# LPDDR4.net
KiCad netlist of a schematic drawn in Altium Designer
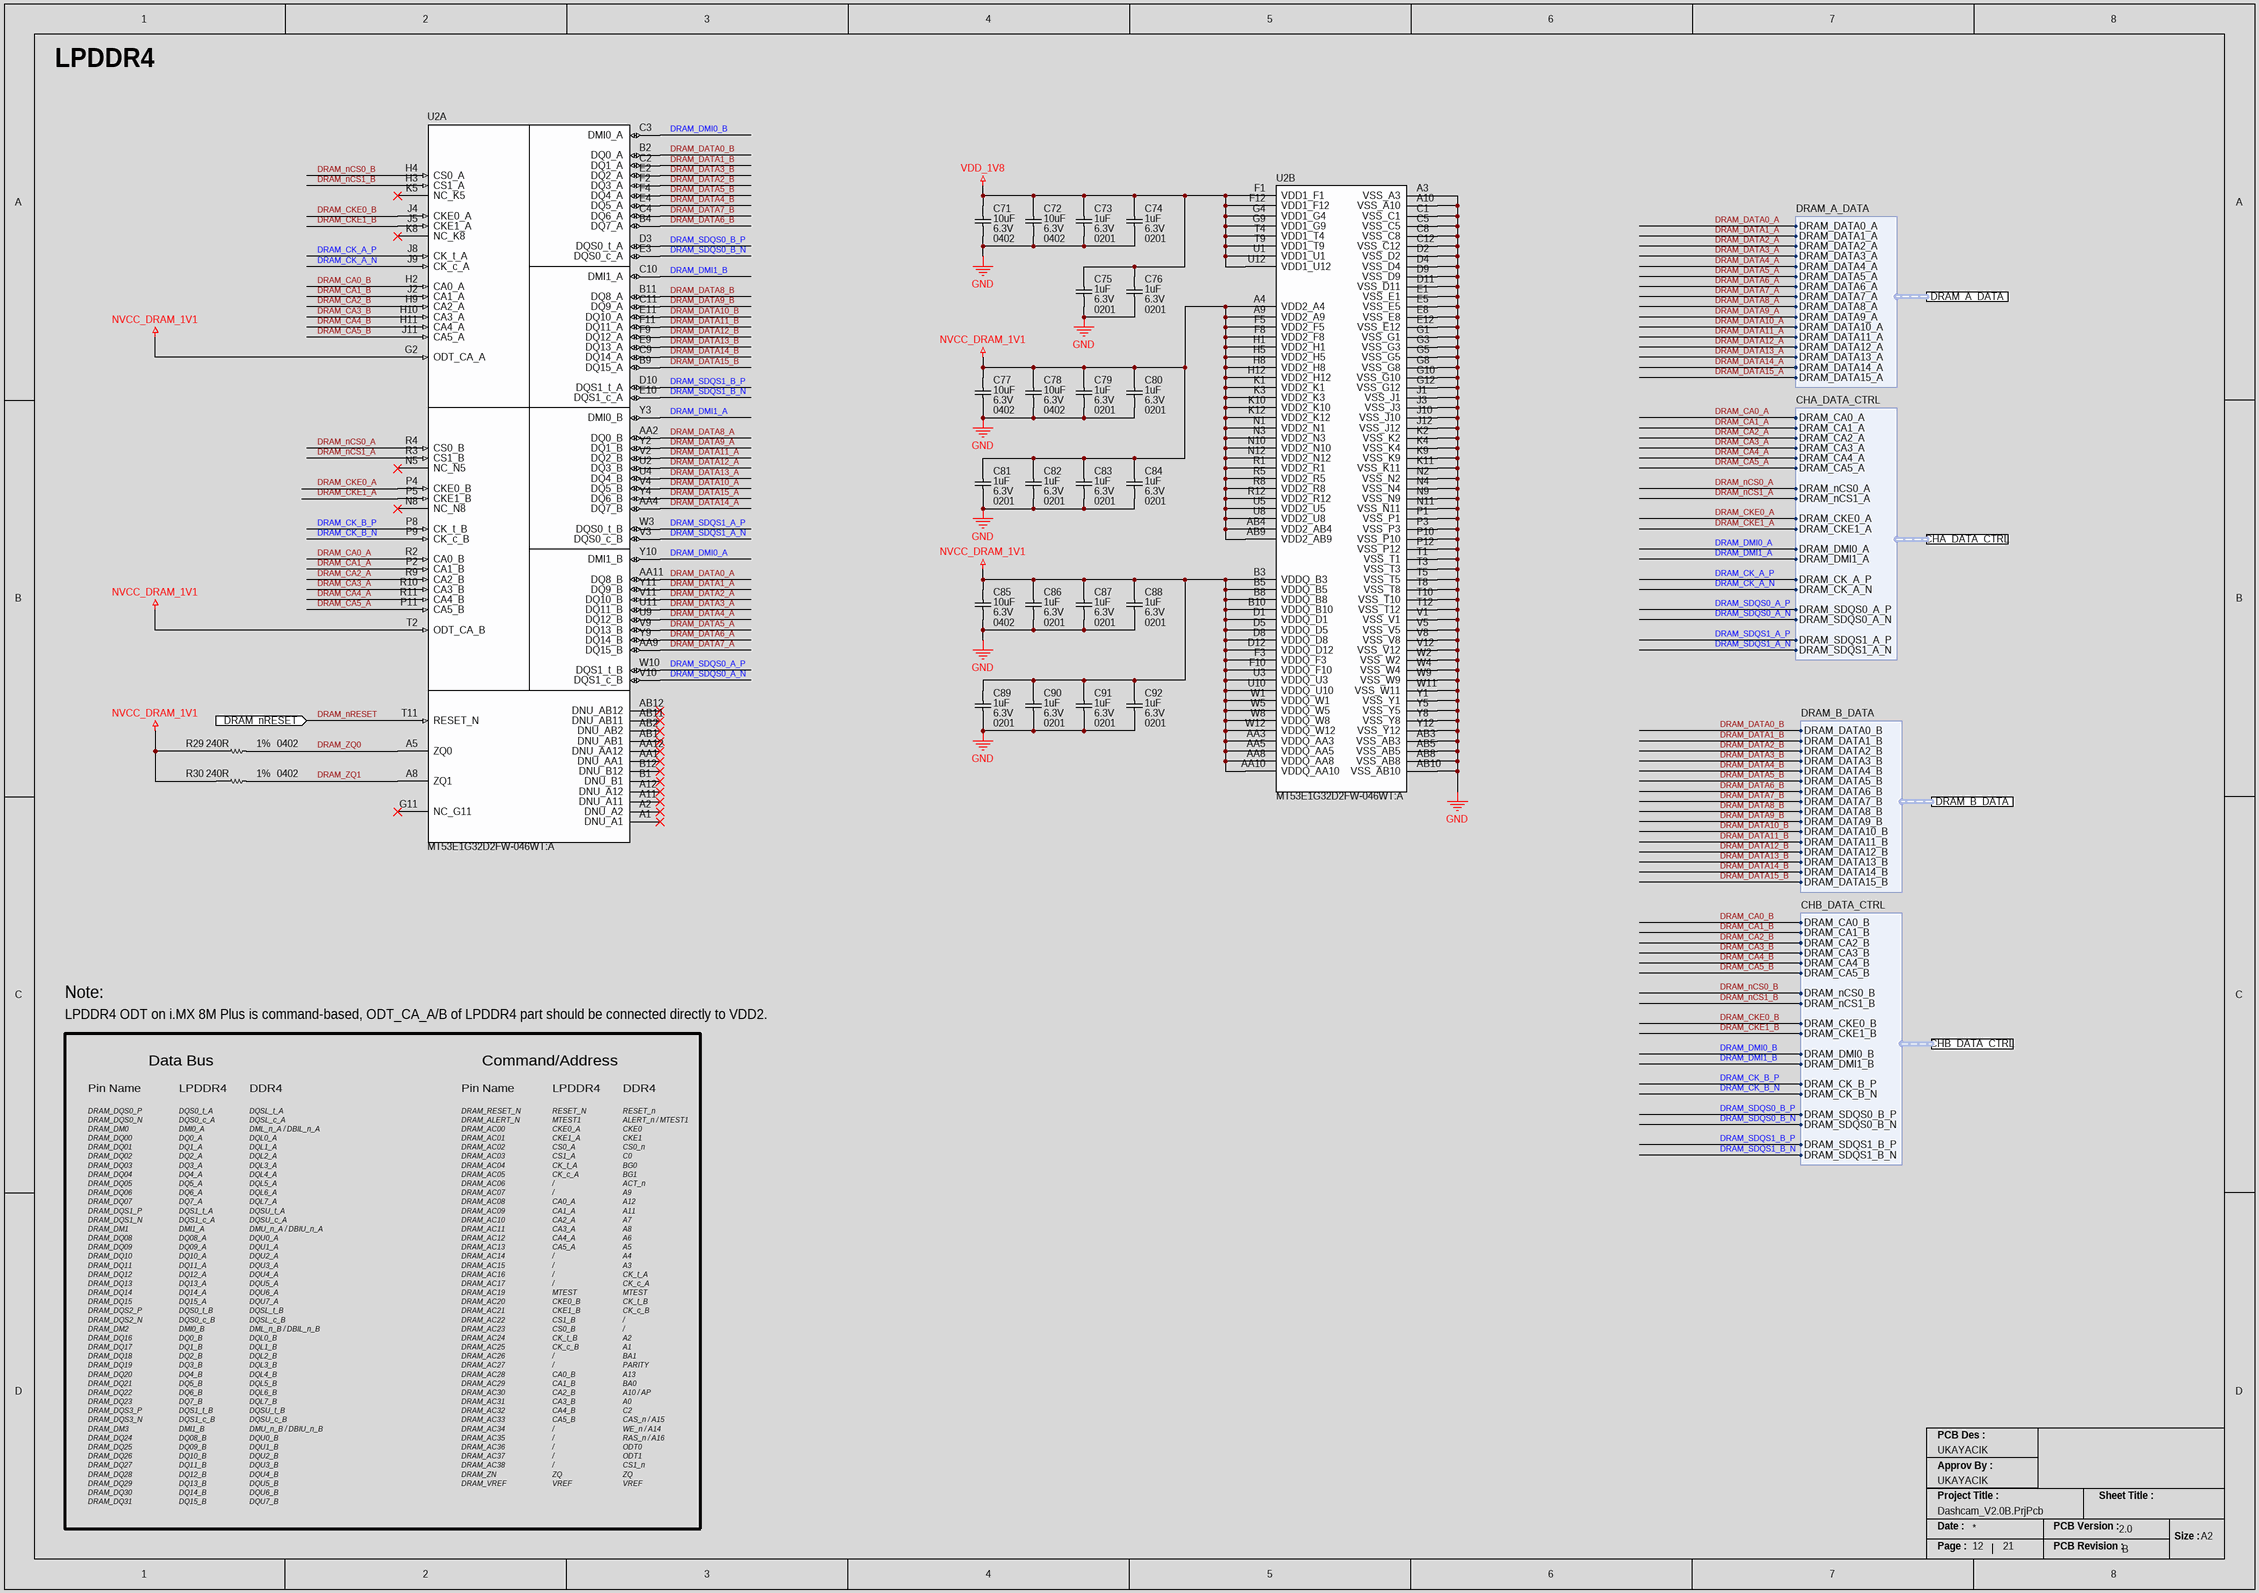
[diagram p0: LPDDR4.SchDoc]

(export (version "E")
  (design (tool "Eeschema 10.0.6"))
  (components
    (comp (ref "C71")
      (value "CL05A106MQ5NUNC")
      (footprint "CAP_0402_CAPC1005X05N")
      (description "Cap Ceramic 10uF 6.3V X5R 20% SMD 0402 85C T/R")
      (fields
        (field (name "MANUFACTURER") "Samsung")
        (field (name "TOLERANCE") "20%")
        (field (name "CASE/PACKAGE") "0402")
        (field (name "CAPACITANCE") "10uF")
        (field (name "VOLTAGE RATING") "6.3V")
      )
      (libsource (lib "Electronic Devices_LIB") (part "CAP_10UF_6.3V_X5R_0402"))
    )
    (comp (ref "C72")
      (value "CL05A106MQ5NUNC")
      (footprint "CAP_0402_CAPC1005X05N")
      (description "Cap Ceramic 10uF 6.3V X5R 20% SMD 0402 85C T/R")
      (fields
        (field (name "MANUFACTURER") "Samsung")
        (field (name "TOLERANCE") "20%")
        (field (name "CASE/PACKAGE") "0402")
        (field (name "CAPACITANCE") "10uF")
        (field (name "VOLTAGE RATING") "6.3V")
      )
      (libsource (lib "Electronic Devices_LIB") (part "CAP_10UF_6.3V_X5R_0402"))
    )
    (comp (ref "C73")
      (value "02016D105MAT2A")
      (footprint "CAP_0201_CAPC0603X03N")
      (description "0201 1 uF 6.3 V ±20 % Tolerance X5R Surface Mount Multilayer Ceramic Capacitor")
      (fields
        (field (name "MANUFACTURER") "Kyocera AVX")
        (field (name "TOLERANCE") "20%")
        (field (name "VOLTAGE RATING (DC)") "6.3V")
        (field (name "CAPACITANCE") "1uF")
        (field (name "CASE/PACKAGE") "0201")
      )
      (libsource (lib "Electronic Devices_LIB") (part "CAP_1UF_6.3V_X5R_0201"))
    )
    (comp (ref "C74")
      (value "02016D105MAT2A")
      (footprint "CAP_0201_CAPC0603X03N")
      (description "0201 1 uF 6.3 V ±20 % Tolerance X5R Surface Mount Multilayer Ceramic Capacitor")
      (fields
        (field (name "MANUFACTURER") "Kyocera AVX")
        (field (name "TOLERANCE") "20%")
        (field (name "VOLTAGE RATING (DC)") "6.3V")
        (field (name "CAPACITANCE") "1uF")
        (field (name "CASE/PACKAGE") "0201")
      )
      (libsource (lib "Electronic Devices_LIB") (part "CAP_1UF_6.3V_X5R_0201"))
    )
    (comp (ref "C75")
      (value "02016D105MAT2A")
      (footprint "CAP_0201_CAPC0603X03N")
      (description "0201 1 uF 6.3 V ±20 % Tolerance X5R Surface Mount Multilayer Ceramic Capacitor")
      (fields
        (field (name "MANUFACTURER") "Kyocera AVX")
        (field (name "TOLERANCE") "20%")
        (field (name "VOLTAGE RATING (DC)") "6.3V")
        (field (name "CAPACITANCE") "1uF")
        (field (name "CASE/PACKAGE") "0201")
      )
      (libsource (lib "Electronic Devices_LIB") (part "CAP_1UF_6.3V_X5R_0201"))
    )
    (comp (ref "C76")
      (value "02016D105MAT2A")
      (footprint "CAP_0201_CAPC0603X03N")
      (description "0201 1 uF 6.3 V ±20 % Tolerance X5R Surface Mount Multilayer Ceramic Capacitor")
      (fields
        (field (name "MANUFACTURER") "Kyocera AVX")
        (field (name "TOLERANCE") "20%")
        (field (name "VOLTAGE RATING (DC)") "6.3V")
        (field (name "CAPACITANCE") "1uF")
        (field (name "CASE/PACKAGE") "0201")
      )
      (libsource (lib "Electronic Devices_LIB") (part "CAP_1UF_6.3V_X5R_0201"))
    )
    (comp (ref "C77")
      (value "CL05A106MQ5NUNC")
      (footprint "CAP_0402_CAPC1005X05N")
      (description "Cap Ceramic 10uF 6.3V X5R 20% SMD 0402 85C T/R")
      (fields
        (field (name "MANUFACTURER") "Samsung")
        (field (name "TOLERANCE") "20%")
        (field (name "CASE/PACKAGE") "0402")
        (field (name "CAPACITANCE") "10uF")
        (field (name "VOLTAGE RATING") "6.3V")
      )
      (libsource (lib "Electronic Devices_LIB") (part "CAP_10UF_6.3V_X5R_0402"))
    )
    (comp (ref "C78")
      (value "CL05A106MQ5NUNC")
      (footprint "CAP_0402_CAPC1005X05N")
      (description "Cap Ceramic 10uF 6.3V X5R 20% SMD 0402 85C T/R")
      (fields
        (field (name "MANUFACTURER") "Samsung")
        (field (name "TOLERANCE") "20%")
        (field (name "CASE/PACKAGE") "0402")
        (field (name "CAPACITANCE") "10uF")
        (field (name "VOLTAGE RATING") "6.3V")
      )
      (libsource (lib "Electronic Devices_LIB") (part "CAP_10UF_6.3V_X5R_0402"))
    )
    (comp (ref "C79")
      (value "02016D105MAT2A")
      (footprint "CAP_0201_CAPC0603X03N")
      (description "0201 1 uF 6.3 V ±20 % Tolerance X5R Surface Mount Multilayer Ceramic Capacitor")
      (fields
        (field (name "MANUFACTURER") "Kyocera AVX")
        (field (name "TOLERANCE") "20%")
        (field (name "VOLTAGE RATING (DC)") "6.3V")
        (field (name "CAPACITANCE") "1uF")
        (field (name "CASE/PACKAGE") "0201")
      )
      (libsource (lib "Electronic Devices_LIB") (part "CAP_1UF_6.3V_X5R_0201"))
    )
    (comp (ref "C80")
      (value "02016D105MAT2A")
      (footprint "CAP_0201_CAPC0603X03N")
      (description "0201 1 uF 6.3 V ±20 % Tolerance X5R Surface Mount Multilayer Ceramic Capacitor")
      (fields
        (field (name "MANUFACTURER") "Kyocera AVX")
        (field (name "TOLERANCE") "20%")
        (field (name "VOLTAGE RATING (DC)") "6.3V")
        (field (name "CAPACITANCE") "1uF")
        (field (name "CASE/PACKAGE") "0201")
      )
      (libsource (lib "Electronic Devices_LIB") (part "CAP_1UF_6.3V_X5R_0201"))
    )
    (comp (ref "C81")
      (value "02016D105MAT2A")
      (footprint "CAP_0201_CAPC0603X03N")
      (description "0201 1 uF 6.3 V ±20 % Tolerance X5R Surface Mount Multilayer Ceramic Capacitor")
      (fields
        (field (name "MANUFACTURER") "Kyocera AVX")
        (field (name "TOLERANCE") "20%")
        (field (name "VOLTAGE RATING (DC)") "6.3V")
        (field (name "CAPACITANCE") "1uF")
        (field (name "CASE/PACKAGE") "0201")
      )
      (libsource (lib "Electronic Devices_LIB") (part "CAP_1UF_6.3V_X5R_0201"))
    )
    (comp (ref "C82")
      (value "02016D105MAT2A")
      (footprint "CAP_0201_CAPC0603X03N")
      (description "0201 1 uF 6.3 V ±20 % Tolerance X5R Surface Mount Multilayer Ceramic Capacitor")
      (fields
        (field (name "MANUFACTURER") "Kyocera AVX")
        (field (name "TOLERANCE") "20%")
        (field (name "VOLTAGE RATING (DC)") "6.3V")
        (field (name "CAPACITANCE") "1uF")
        (field (name "CASE/PACKAGE") "0201")
      )
      (libsource (lib "Electronic Devices_LIB") (part "CAP_1UF_6.3V_X5R_0201"))
    )
    (comp (ref "C83")
      (value "02016D105MAT2A")
      (footprint "CAP_0201_CAPC0603X03N")
      (description "0201 1 uF 6.3 V ±20 % Tolerance X5R Surface Mount Multilayer Ceramic Capacitor")
      (fields
        (field (name "MANUFACTURER") "Kyocera AVX")
        (field (name "TOLERANCE") "20%")
        (field (name "VOLTAGE RATING (DC)") "6.3V")
        (field (name "CAPACITANCE") "1uF")
        (field (name "CASE/PACKAGE") "0201")
      )
      (libsource (lib "Electronic Devices_LIB") (part "CAP_1UF_6.3V_X5R_0201"))
    )
    (comp (ref "C84")
      (value "02016D105MAT2A")
      (footprint "CAP_0201_CAPC0603X03N")
      (description "0201 1 uF 6.3 V ±20 % Tolerance X5R Surface Mount Multilayer Ceramic Capacitor")
      (fields
        (field (name "MANUFACTURER") "Kyocera AVX")
        (field (name "TOLERANCE") "20%")
        (field (name "VOLTAGE RATING (DC)") "6.3V")
        (field (name "CAPACITANCE") "1uF")
        (field (name "CASE/PACKAGE") "0201")
      )
      (libsource (lib "Electronic Devices_LIB") (part "CAP_1UF_6.3V_X5R_0201"))
    )
    (comp (ref "C85")
      (value "CL05A106MQ5NUNC")
      (footprint "CAP_0402_CAPC1005X05N")
      (description "Cap Ceramic 10uF 6.3V X5R 20% SMD 0402 85C T/R")
      (fields
        (field (name "MANUFACTURER") "Samsung")
        (field (name "TOLERANCE") "20%")
        (field (name "CASE/PACKAGE") "0402")
        (field (name "CAPACITANCE") "10uF")
        (field (name "VOLTAGE RATING") "6.3V")
      )
      (libsource (lib "Electronic Devices_LIB") (part "CAP_10UF_6.3V_X5R_0402"))
    )
    (comp (ref "C86")
      (value "02016D105MAT2A")
      (footprint "CAP_0201_CAPC0603X03N")
      (description "0201 1 uF 6.3 V ±20 % Tolerance X5R Surface Mount Multilayer Ceramic Capacitor")
      (fields
        (field (name "MANUFACTURER") "Kyocera AVX")
        (field (name "TOLERANCE") "20%")
        (field (name "VOLTAGE RATING (DC)") "6.3V")
        (field (name "CAPACITANCE") "1uF")
        (field (name "CASE/PACKAGE") "0201")
      )
      (libsource (lib "Electronic Devices_LIB") (part "CAP_1UF_6.3V_X5R_0201"))
    )
    (comp (ref "C87")
      (value "02016D105MAT2A")
      (footprint "CAP_0201_CAPC0603X03N")
      (description "0201 1 uF 6.3 V ±20 % Tolerance X5R Surface Mount Multilayer Ceramic Capacitor")
      (fields
        (field (name "MANUFACTURER") "Kyocera AVX")
        (field (name "TOLERANCE") "20%")
        (field (name "VOLTAGE RATING (DC)") "6.3V")
        (field (name "CAPACITANCE") "1uF")
        (field (name "CASE/PACKAGE") "0201")
      )
      (libsource (lib "Electronic Devices_LIB") (part "CAP_1UF_6.3V_X5R_0201"))
    )
    (comp (ref "C88")
      (value "02016D105MAT2A")
      (footprint "CAP_0201_CAPC0603X03N")
      (description "0201 1 uF 6.3 V ±20 % Tolerance X5R Surface Mount Multilayer Ceramic Capacitor")
      (fields
        (field (name "MANUFACTURER") "Kyocera AVX")
        (field (name "TOLERANCE") "20%")
        (field (name "VOLTAGE RATING (DC)") "6.3V")
        (field (name "CAPACITANCE") "1uF")
        (field (name "CASE/PACKAGE") "0201")
      )
      (libsource (lib "Electronic Devices_LIB") (part "CAP_1UF_6.3V_X5R_0201"))
    )
    (comp (ref "C89")
      (value "02016D105MAT2A")
      (footprint "CAP_0201_CAPC0603X03N")
      (description "0201 1 uF 6.3 V ±20 % Tolerance X5R Surface Mount Multilayer Ceramic Capacitor")
      (fields
        (field (name "MANUFACTURER") "Kyocera AVX")
        (field (name "TOLERANCE") "20%")
        (field (name "VOLTAGE RATING (DC)") "6.3V")
        (field (name "CAPACITANCE") "1uF")
        (field (name "CASE/PACKAGE") "0201")
      )
      (libsource (lib "Electronic Devices_LIB") (part "CAP_1UF_6.3V_X5R_0201"))
    )
    (comp (ref "C90")
      (value "02016D105MAT2A")
      (footprint "CAP_0201_CAPC0603X03N")
      (description "0201 1 uF 6.3 V ±20 % Tolerance X5R Surface Mount Multilayer Ceramic Capacitor")
      (fields
        (field (name "MANUFACTURER") "Kyocera AVX")
        (field (name "TOLERANCE") "20%")
        (field (name "VOLTAGE RATING (DC)") "6.3V")
        (field (name "CAPACITANCE") "1uF")
        (field (name "CASE/PACKAGE") "0201")
      )
      (libsource (lib "Electronic Devices_LIB") (part "CAP_1UF_6.3V_X5R_0201"))
    )
    (comp (ref "C91")
      (value "02016D105MAT2A")
      (footprint "CAP_0201_CAPC0603X03N")
      (description "0201 1 uF 6.3 V ±20 % Tolerance X5R Surface Mount Multilayer Ceramic Capacitor")
      (fields
        (field (name "MANUFACTURER") "Kyocera AVX")
        (field (name "TOLERANCE") "20%")
        (field (name "VOLTAGE RATING (DC)") "6.3V")
        (field (name "CAPACITANCE") "1uF")
        (field (name "CASE/PACKAGE") "0201")
      )
      (libsource (lib "Electronic Devices_LIB") (part "CAP_1UF_6.3V_X5R_0201"))
    )
    (comp (ref "C92")
      (value "02016D105MAT2A")
      (footprint "CAP_0201_CAPC0603X03N")
      (description "0201 1 uF 6.3 V ±20 % Tolerance X5R Surface Mount Multilayer Ceramic Capacitor")
      (fields
        (field (name "MANUFACTURER") "Kyocera AVX")
        (field (name "TOLERANCE") "20%")
        (field (name "VOLTAGE RATING (DC)") "6.3V")
        (field (name "CAPACITANCE") "1uF")
        (field (name "CASE/PACKAGE") "0201")
      )
      (libsource (lib "Electronic Devices_LIB") (part "CAP_1UF_6.3V_X5R_0201"))
    )
    (comp (ref "R29")
      (value "RC0402FR-07240RL")
      (footprint "RES_0402_RESC1005X04N")
      (description "SMD Chip Resistor, 240 Ohm, ± 1%, 63 mW, 0402 [1005 Metric], Thick Film, General Purpose")
      (fields
        (field (name "MANUFACTURER") "Yageo")
        (field (name "TOLERANCE") "1%")
        (field (name "RESISTANCE") "240R")
        (field (name "CASE/PACKAGE") "0402")
      )
      (libsource (lib "Electronic Devices_LIB") (part "RES_240R_1%_63mW_0402"))
    )
    (comp (ref "R30")
      (value "RC0402FR-07240RL")
      (footprint "RES_0402_RESC1005X04N")
      (description "SMD Chip Resistor, 240 Ohm, ± 1%, 63 mW, 0402 [1005 Metric], Thick Film, General Purpose")
      (fields
        (field (name "MANUFACTURER") "Yageo")
        (field (name "TOLERANCE") "1%")
        (field (name "RESISTANCE") "240R")
        (field (name "CASE/PACKAGE") "0402")
      )
      (libsource (lib "Electronic Devices_LIB") (part "RES_240R_1%_63mW_0402"))
    )
    (comp (ref "U2")
      (value "MT53E1G32D2FW-046WT:A")
      (footprint "IC_DRAM_BGA200_0P65X0P8_10P1X14P6")
      (description "LPDDR4 32G 1GX32 FBGA DDP")
      (fields (field (name "MANUFACTURER") "Micron Technology"))
      (libsource (lib "Electronic Devices_LIB") (part "IC_DRAM_32G_MT53E1G32D2FW-046WT{colon}A"))
    )
  )
  (nets
    (net (code "5") (name "/DRAM_CA0_A") (class "Default")
      (node (ref "U2") (pin "R2") (pinfunction "CA0_B_R2") (pintype "input"))
    )
    (net (code "6") (name "/DRAM_CA0_B") (class "Default")
      (node (ref "U2") (pin "H2") (pinfunction "CA0_A_H2") (pintype "input"))
    )
    (net (code "7") (name "/DRAM_CA1_A") (class "Default")
      (node (ref "U2") (pin "P2") (pinfunction "CA1_B_P2") (pintype "input"))
    )
    (net (code "8") (name "/DRAM_CA1_B") (class "Default")
      (node (ref "U2") (pin "J2") (pinfunction "CA1_A_J2") (pintype "input"))
    )
    (net (code "9") (name "/DRAM_CA2_A") (class "Default")
      (node (ref "U2") (pin "R9") (pinfunction "CA2_B_R9") (pintype "input"))
    )
    (net (code "10") (name "/DRAM_CA2_B") (class "Default")
      (node (ref "U2") (pin "H9") (pinfunction "CA2_A_H9") (pintype "input"))
    )
    (net (code "11") (name "/DRAM_CA3_A") (class "Default")
      (node (ref "U2") (pin "R10") (pinfunction "CA3_B_R10") (pintype "input"))
    )
    (net (code "12") (name "/DRAM_CA3_B") (class "Default")
      (node (ref "U2") (pin "H10") (pinfunction "CA3_A_H10") (pintype "input"))
    )
    (net (code "13") (name "/DRAM_CA4_A") (class "Default")
      (node (ref "U2") (pin "R11") (pinfunction "CA4_B_R11") (pintype "input"))
    )
    (net (code "14") (name "/DRAM_CA4_B") (class "Default")
      (node (ref "U2") (pin "H11") (pinfunction "CA4_A_H11") (pintype "input"))
    )
    (net (code "15") (name "/DRAM_CA5_A") (class "Default")
      (node (ref "U2") (pin "P11") (pinfunction "CA5_B_P11") (pintype "input"))
    )
    (net (code "16") (name "/DRAM_CA5_B") (class "Default")
      (node (ref "U2") (pin "J11") (pinfunction "CA5_A_J11") (pintype "input"))
    )
    (net (code "17") (name "/DRAM_CKE0_A") (class "Default")
      (node (ref "U2") (pin "P4") (pinfunction "CKE0_B_P4") (pintype "input"))
    )
    (net (code "18") (name "/DRAM_CKE0_B") (class "Default")
      (node (ref "U2") (pin "J4") (pinfunction "CKE0_A_J4") (pintype "input"))
    )
    (net (code "19") (name "/DRAM_CKE1_A") (class "Default")
      (node (ref "U2") (pin "P5") (pinfunction "CKE1_B_P5") (pintype "input"))
    )
    (net (code "20") (name "/DRAM_CKE1_B") (class "Default")
      (node (ref "U2") (pin "J5") (pinfunction "CKE1_A_J5") (pintype "input"))
    )
    (net (code "21") (name "/DRAM_CK_A_N") (class "Default")
      (node (ref "U2") (pin "J9") (pinfunction "CK_c_A_J9") (pintype "input"))
    )
    (net (code "22") (name "/DRAM_CK_A_P") (class "Default")
      (node (ref "U2") (pin "J8") (pinfunction "CK_t_A_J8") (pintype "input"))
    )
    (net (code "23") (name "/DRAM_CK_B_N") (class "Default")
      (node (ref "U2") (pin "P9") (pinfunction "CK_c_B_P9") (pintype "input"))
    )
    (net (code "24") (name "/DRAM_CK_B_P") (class "Default")
      (node (ref "U2") (pin "P8") (pinfunction "CK_t_B_P8") (pintype "input"))
    )
    (net (code "25") (name "/DRAM_DATA0_A") (class "Default")
      (node (ref "U2") (pin "AA11") (pinfunction "DQ8_B_AA11") (pintype "bidirectional"))
    )
    (net (code "26") (name "/DRAM_DATA0_B") (class "Default")
      (node (ref "U2") (pin "B2") (pinfunction "DQ0_A_B2") (pintype "bidirectional"))
    )
    (net (code "27") (name "/DRAM_DATA1_A") (class "Default")
      (node (ref "U2") (pin "Y11") (pinfunction "DQ9_B_Y11") (pintype "bidirectional"))
    )
    (net (code "28") (name "/DRAM_DATA1_B") (class "Default")
      (node (ref "U2") (pin "C2") (pinfunction "DQ1_A_C2") (pintype "bidirectional"))
    )
    (net (code "29") (name "/DRAM_DATA2_A") (class "Default")
      (node (ref "U2") (pin "V11") (pinfunction "DQ10_B_V11") (pintype "bidirectional"))
    )
    (net (code "30") (name "/DRAM_DATA2_B") (class "Default")
      (node (ref "U2") (pin "F2") (pinfunction "DQ3_A_F2") (pintype "bidirectional"))
    )
    (net (code "31") (name "/DRAM_DATA3_A") (class "Default")
      (node (ref "U2") (pin "U11") (pinfunction "DQ11_B_U11") (pintype "bidirectional"))
    )
    (net (code "32") (name "/DRAM_DATA3_B") (class "Default")
      (node (ref "U2") (pin "E2") (pinfunction "DQ2_A_E2") (pintype "bidirectional"))
    )
    (net (code "33") (name "/DRAM_DATA4_A") (class "Default")
      (node (ref "U2") (pin "U9") (pinfunction "DQ12_B_U9") (pintype "bidirectional"))
    )
    (net (code "34") (name "/DRAM_DATA4_B") (class "Default")
      (node (ref "U2") (pin "E4") (pinfunction "DQ5_A_E4") (pintype "bidirectional"))
    )
    (net (code "35") (name "/DRAM_DATA5_A") (class "Default")
      (node (ref "U2") (pin "V9") (pinfunction "DQ13_B_V9") (pintype "bidirectional"))
    )
    (net (code "36") (name "/DRAM_DATA5_B") (class "Default")
      (node (ref "U2") (pin "F4") (pinfunction "DQ4_A_F4") (pintype "bidirectional"))
    )
    (net (code "37") (name "/DRAM_DATA6_A") (class "Default")
      (node (ref "U2") (pin "Y9") (pinfunction "DQ14_B_Y9") (pintype "bidirectional"))
    )
    (net (code "38") (name "/DRAM_DATA6_B") (class "Default")
      (node (ref "U2") (pin "B4") (pinfunction "DQ7_A_B4") (pintype "bidirectional"))
    )
    (net (code "39") (name "/DRAM_DATA7_A") (class "Default")
      (node (ref "U2") (pin "AA9") (pinfunction "DQ15_B_AA9") (pintype "bidirectional"))
    )
    (net (code "40") (name "/DRAM_DATA7_B") (class "Default")
      (node (ref "U2") (pin "C4") (pinfunction "DQ6_A_C4") (pintype "bidirectional"))
    )
    (net (code "41") (name "/DRAM_DATA8_A") (class "Default")
      (node (ref "U2") (pin "AA2") (pinfunction "DQ0_B_AA2") (pintype "bidirectional"))
    )
    (net (code "42") (name "/DRAM_DATA8_B") (class "Default")
      (node (ref "U2") (pin "B11") (pinfunction "DQ8_A_B11") (pintype "bidirectional"))
    )
    (net (code "43") (name "/DRAM_DATA9_A") (class "Default")
      (node (ref "U2") (pin "Y2") (pinfunction "DQ1_B_Y2") (pintype "bidirectional"))
    )
    (net (code "44") (name "/DRAM_DATA9_B") (class "Default")
      (node (ref "U2") (pin "C11") (pinfunction "DQ9_A_C11") (pintype "bidirectional"))
    )
    (net (code "45") (name "/DRAM_DATA10_A") (class "Default")
      (node (ref "U2") (pin "V4") (pinfunction "DQ5_B_V4") (pintype "bidirectional"))
    )
    (net (code "46") (name "/DRAM_DATA10_B") (class "Default")
      (node (ref "U2") (pin "E11") (pinfunction "DQ10_A_E11") (pintype "bidirectional"))
    )
    (net (code "47") (name "/DRAM_DATA11_A") (class "Default")
      (node (ref "U2") (pin "V2") (pinfunction "DQ2_B_V2") (pintype "bidirectional"))
    )
    (net (code "48") (name "/DRAM_DATA11_B") (class "Default")
      (node (ref "U2") (pin "F11") (pinfunction "DQ11_A_F11") (pintype "bidirectional"))
    )
    (net (code "49") (name "/DRAM_DATA12_A") (class "Default")
      (node (ref "U2") (pin "U2") (pinfunction "DQ3_B_U2") (pintype "bidirectional"))
    )
    (net (code "50") (name "/DRAM_DATA12_B") (class "Default")
      (node (ref "U2") (pin "F9") (pinfunction "DQ12_A_F9") (pintype "bidirectional"))
    )
    (net (code "51") (name "/DRAM_DATA13_A") (class "Default")
      (node (ref "U2") (pin "U4") (pinfunction "DQ4_B_U4") (pintype "bidirectional"))
    )
    (net (code "52") (name "/DRAM_DATA13_B") (class "Default")
      (node (ref "U2") (pin "E9") (pinfunction "DQ13_A_E9") (pintype "bidirectional"))
    )
    (net (code "53") (name "/DRAM_DATA14_A") (class "Default")
      (node (ref "U2") (pin "AA4") (pinfunction "DQ7_B_AA4") (pintype "bidirectional"))
    )
    (net (code "54") (name "/DRAM_DATA14_B") (class "Default")
      (node (ref "U2") (pin "C9") (pinfunction "DQ14_A_C9") (pintype "bidirectional"))
    )
    (net (code "55") (name "/DRAM_DATA15_A") (class "Default")
      (node (ref "U2") (pin "Y4") (pinfunction "DQ6_B_Y4") (pintype "bidirectional"))
    )
    (net (code "56") (name "/DRAM_DATA15_B") (class "Default")
      (node (ref "U2") (pin "B9") (pinfunction "DQ15_A_B9") (pintype "bidirectional"))
    )
    (net (code "57") (name "/DRAM_DMI0_A") (class "Default")
      (node (ref "U2") (pin "Y10") (pinfunction "DMI1_B_Y10") (pintype "bidirectional"))
    )
    (net (code "58") (name "/DRAM_DMI0_B") (class "Default")
      (node (ref "U2") (pin "C3") (pinfunction "DMI0_A_C3") (pintype "bidirectional"))
    )
    (net (code "59") (name "/DRAM_DMI1_A") (class "Default")
      (node (ref "U2") (pin "Y3") (pinfunction "DMI0_B_Y3") (pintype "bidirectional"))
    )
    (net (code "60") (name "/DRAM_DMI1_B") (class "Default")
      (node (ref "U2") (pin "C10") (pinfunction "DMI1_A_C10") (pintype "bidirectional"))
    )
    (net (code "61") (name "/DRAM_SDQS0_A_N") (class "Default")
      (node (ref "U2") (pin "V10") (pinfunction "DQS1_c_B_V10") (pintype "bidirectional"))
    )
    (net (code "62") (name "/DRAM_SDQS0_A_P") (class "Default")
      (node (ref "U2") (pin "W10") (pinfunction "DQS1_t_B_W10") (pintype "bidirectional"))
    )
    (net (code "63") (name "/DRAM_SDQS0_B_N") (class "Default")
      (node (ref "U2") (pin "E3") (pinfunction "DQS0_c_A_E3") (pintype "bidirectional"))
    )
    (net (code "64") (name "/DRAM_SDQS0_B_P") (class "Default")
      (node (ref "U2") (pin "D3") (pinfunction "DQS0_t_A_D3") (pintype "bidirectional"))
    )
    (net (code "65") (name "/DRAM_SDQS1_A_N") (class "Default")
      (node (ref "U2") (pin "V3") (pinfunction "DQS0_c_B_V3") (pintype "bidirectional"))
    )
    (net (code "66") (name "/DRAM_SDQS1_A_P") (class "Default")
      (node (ref "U2") (pin "W3") (pinfunction "DQS0_t_B_W3") (pintype "bidirectional"))
    )
    (net (code "67") (name "/DRAM_SDQS1_B_N") (class "Default")
      (node (ref "U2") (pin "E10") (pinfunction "DQS1_c_A_E10") (pintype "bidirectional"))
    )
    (net (code "68") (name "/DRAM_SDQS1_B_P") (class "Default")
      (node (ref "U2") (pin "D10") (pinfunction "DQS1_t_A_D10") (pintype "bidirectional"))
    )
    (net (code "69") (name "/DRAM_ZQ0") (class "Default")
      (node (ref "R29") (pin "2") (pinfunction "2_2") (pintype "passive"))
      (node (ref "U2") (pin "A5") (pinfunction "ZQ0_A5") (pintype "passive"))
    )
    (net (code "70") (name "/DRAM_ZQ1") (class "Default")
      (node (ref "R30") (pin "2") (pinfunction "2_2") (pintype "passive"))
      (node (ref "U2") (pin "A8") (pinfunction "ZQ1_A8") (pintype "passive"))
    )
    (net (code "71") (name "/DRAM_nCS0_A") (class "Default")
      (node (ref "U2") (pin "R4") (pinfunction "CS0_B_R4") (pintype "input"))
    )
    (net (code "72") (name "/DRAM_nCS0_B") (class "Default")
      (node (ref "U2") (pin "H4") (pinfunction "CS0_A_H4") (pintype "input"))
    )
    (net (code "73") (name "/DRAM_nCS1_A") (class "Default")
      (node (ref "U2") (pin "R3") (pinfunction "CS1_B_R3") (pintype "input"))
    )
    (net (code "74") (name "/DRAM_nCS1_B") (class "Default")
      (node (ref "U2") (pin "H3") (pinfunction "CS1_A_H3") (pintype "input"))
    )
    (net (code "75") (name "/DRAM_nRESET") (class "Default")
      (node (ref "U2") (pin "T11") (pinfunction "RESET_N_T11") (pintype "input"))
    )
    (net (code "80") (name "GND") (class "Default")
      (node (ref "C71") (pin "1") (pinfunction "1_1") (pintype "passive"))
      (node (ref "C72") (pin "1") (pinfunction "1_1") (pintype "passive"))
      (node (ref "C73") (pin "1") (pinfunction "1_1") (pintype "passive"))
      (node (ref "C74") (pin "1") (pinfunction "1_1") (pintype "passive"))
      (node (ref "C75") (pin "1") (pinfunction "1_1") (pintype "passive"))
      (node (ref "C76") (pin "1") (pinfunction "1_1") (pintype "passive"))
      (node (ref "C77") (pin "1") (pinfunction "1_1") (pintype "passive"))
      (node (ref "C78") (pin "1") (pinfunction "1_1") (pintype "passive"))
      (node (ref "C79") (pin "1") (pinfunction "1_1") (pintype "passive"))
      (node (ref "C80") (pin "1") (pinfunction "1_1") (pintype "passive"))
      (node (ref "C81") (pin "1") (pinfunction "1_1") (pintype "passive"))
      (node (ref "C82") (pin "1") (pinfunction "1_1") (pintype "passive"))
      (node (ref "C83") (pin "1") (pinfunction "1_1") (pintype "passive"))
      (node (ref "C84") (pin "1") (pinfunction "1_1") (pintype "passive"))
      (node (ref "C85") (pin "1") (pinfunction "1_1") (pintype "passive"))
      (node (ref "C86") (pin "1") (pinfunction "1_1") (pintype "passive"))
      (node (ref "C87") (pin "1") (pinfunction "1_1") (pintype "passive"))
      (node (ref "C88") (pin "1") (pinfunction "1_1") (pintype "passive"))
      (node (ref "C89") (pin "1") (pinfunction "1_1") (pintype "passive"))
      (node (ref "C90") (pin "1") (pinfunction "1_1") (pintype "passive"))
      (node (ref "C91") (pin "1") (pinfunction "1_1") (pintype "passive"))
      (node (ref "C92") (pin "1") (pinfunction "1_1") (pintype "passive"))
      (node (ref "U2") (pin "A10") (pinfunction "VSS_A10_A10") (pintype "power_in"))
      (node (ref "U2") (pin "A3") (pinfunction "VSS_A3_A3") (pintype "power_in"))
      (node (ref "U2") (pin "AB10") (pinfunction "VSS_AB10_AB10") (pintype "power_in"))
      (node (ref "U2") (pin "AB3") (pinfunction "VSS_AB3_AB3") (pintype "power_in"))
      (node (ref "U2") (pin "AB5") (pinfunction "VSS_AB5_AB5") (pintype "power_in"))
      (node (ref "U2") (pin "AB8") (pinfunction "VSS_AB8_AB8") (pintype "power_in"))
      (node (ref "U2") (pin "C1") (pinfunction "VSS_C1_C1") (pintype "power_in"))
      (node (ref "U2") (pin "C12") (pinfunction "VSS_C12_C12") (pintype "power_in"))
      (node (ref "U2") (pin "C5") (pinfunction "VSS_C5_C5") (pintype "power_in"))
      (node (ref "U2") (pin "C8") (pinfunction "VSS_C8_C8") (pintype "power_in"))
      (node (ref "U2") (pin "D11") (pinfunction "VSS_D11_D11") (pintype "power_in"))
      (node (ref "U2") (pin "D2") (pinfunction "VSS_D2_D2") (pintype "power_in"))
      (node (ref "U2") (pin "D4") (pinfunction "VSS_D4_D4") (pintype "power_in"))
      (node (ref "U2") (pin "D9") (pinfunction "VSS_D9_D9") (pintype "power_in"))
      (node (ref "U2") (pin "E1") (pinfunction "VSS_E1_E1") (pintype "power_in"))
      (node (ref "U2") (pin "E12") (pinfunction "VSS_E12_E12") (pintype "power_in"))
      (node (ref "U2") (pin "E5") (pinfunction "VSS_E5_E5") (pintype "power_in"))
      (node (ref "U2") (pin "E8") (pinfunction "VSS_E8_E8") (pintype "power_in"))
      (node (ref "U2") (pin "G1") (pinfunction "VSS_G1_G1") (pintype "power_in"))
      (node (ref "U2") (pin "G10") (pinfunction "VSS_G10_G10") (pintype "power_in"))
      (node (ref "U2") (pin "G12") (pinfunction "VSS_G12_G12") (pintype "power_in"))
      (node (ref "U2") (pin "G3") (pinfunction "VSS_G3_G3") (pintype "power_in"))
      (node (ref "U2") (pin "G5") (pinfunction "VSS_G5_G5") (pintype "power_in"))
      (node (ref "U2") (pin "G8") (pinfunction "VSS_G8_G8") (pintype "power_in"))
      (node (ref "U2") (pin "J1") (pinfunction "VSS_J1_J1") (pintype "power_in"))
      (node (ref "U2") (pin "J10") (pinfunction "VSS_J10_J10") (pintype "power_in"))
      (node (ref "U2") (pin "J12") (pinfunction "VSS_J12_J12") (pintype "power_in"))
      (node (ref "U2") (pin "J3") (pinfunction "VSS_J3_J3") (pintype "power_in"))
      (node (ref "U2") (pin "K11") (pinfunction "VSS_K11_K11") (pintype "power_in"))
      (node (ref "U2") (pin "K2") (pinfunction "VSS_K2_K2") (pintype "power_in"))
      (node (ref "U2") (pin "K4") (pinfunction "VSS_K4_K4") (pintype "power_in"))
      (node (ref "U2") (pin "K9") (pinfunction "VSS_K9_K9") (pintype "power_in"))
      (node (ref "U2") (pin "N11") (pinfunction "VSS_N11_N11") (pintype "power_in"))
      (node (ref "U2") (pin "N2") (pinfunction "VSS_N2_N2") (pintype "power_in"))
      (node (ref "U2") (pin "N4") (pinfunction "VSS_N4_N4") (pintype "power_in"))
      (node (ref "U2") (pin "N9") (pinfunction "VSS_N9_N9") (pintype "power_in"))
      (node (ref "U2") (pin "P1") (pinfunction "VSS_P1_P1") (pintype "power_in"))
      (node (ref "U2") (pin "P10") (pinfunction "VSS_P10_P10") (pintype "power_in"))
      (node (ref "U2") (pin "P12") (pinfunction "VSS_P12_P12") (pintype "power_in"))
      (node (ref "U2") (pin "P3") (pinfunction "VSS_P3_P3") (pintype "power_in"))
      (node (ref "U2") (pin "T1") (pinfunction "VSS_T1_T1") (pintype "power_in"))
      (node (ref "U2") (pin "T10") (pinfunction "VSS_T10_T10") (pintype "power_in"))
      (node (ref "U2") (pin "T12") (pinfunction "VSS_T12_T12") (pintype "power_in"))
      (node (ref "U2") (pin "T3") (pinfunction "VSS_T3_T3") (pintype "power_in"))
      (node (ref "U2") (pin "T5") (pinfunction "VSS_T5_T5") (pintype "power_in"))
      (node (ref "U2") (pin "T8") (pinfunction "VSS_T8_T8") (pintype "power_in"))
      (node (ref "U2") (pin "V1") (pinfunction "VSS_V1_V1") (pintype "power_in"))
      (node (ref "U2") (pin "V12") (pinfunction "VSS_V12_V12") (pintype "power_in"))
      (node (ref "U2") (pin "V5") (pinfunction "VSS_V5_V5") (pintype "power_in"))
      (node (ref "U2") (pin "V8") (pinfunction "VSS_V8_V8") (pintype "power_in"))
      (node (ref "U2") (pin "W11") (pinfunction "VSS_W11_W11") (pintype "power_in"))
      (node (ref "U2") (pin "W2") (pinfunction "VSS_W2_W2") (pintype "power_in"))
      (node (ref "U2") (pin "W4") (pinfunction "VSS_W4_W4") (pintype "power_in"))
      (node (ref "U2") (pin "W9") (pinfunction "VSS_W9_W9") (pintype "power_in"))
      (node (ref "U2") (pin "Y1") (pinfunction "VSS_Y1_Y1") (pintype "power_in"))
      (node (ref "U2") (pin "Y12") (pinfunction "VSS_Y12_Y12") (pintype "power_in"))
      (node (ref "U2") (pin "Y5") (pinfunction "VSS_Y5_Y5") (pintype "power_in"))
      (node (ref "U2") (pin "Y8") (pinfunction "VSS_Y8_Y8") (pintype "power_in"))
    )
    (net (code "81") (name "NVCC_DRAM_1V1") (class "Default")
      (node (ref "C77") (pin "2") (pinfunction "2_2") (pintype "passive"))
      (node (ref "C78") (pin "2") (pinfunction "2_2") (pintype "passive"))
      (node (ref "C79") (pin "2") (pinfunction "2_2") (pintype "passive"))
      (node (ref "C80") (pin "2") (pinfunction "2_2") (pintype "passive"))
      (node (ref "C81") (pin "2") (pinfunction "2_2") (pintype "passive"))
      (node (ref "C82") (pin "2") (pinfunction "2_2") (pintype "passive"))
      (node (ref "C83") (pin "2") (pinfunction "2_2") (pintype "passive"))
      (node (ref "C84") (pin "2") (pinfunction "2_2") (pintype "passive"))
      (node (ref "C85") (pin "2") (pinfunction "2_2") (pintype "passive"))
      (node (ref "C86") (pin "2") (pinfunction "2_2") (pintype "passive"))
      (node (ref "C87") (pin "2") (pinfunction "2_2") (pintype "passive"))
      (node (ref "C88") (pin "2") (pinfunction "2_2") (pintype "passive"))
      (node (ref "C89") (pin "2") (pinfunction "2_2") (pintype "passive"))
      (node (ref "C90") (pin "2") (pinfunction "2_2") (pintype "passive"))
      (node (ref "C91") (pin "2") (pinfunction "2_2") (pintype "passive"))
      (node (ref "C92") (pin "2") (pinfunction "2_2") (pintype "passive"))
      (node (ref "R29") (pin "1") (pinfunction "1_1") (pintype "passive"))
      (node (ref "R30") (pin "1") (pinfunction "1_1") (pintype "passive"))
      (node (ref "U2") (pin "A4") (pinfunction "VDD2_A4_A4") (pintype "power_in"))
      (node (ref "U2") (pin "A9") (pinfunction "VDD2_A9_A9") (pintype "power_in"))
      (node (ref "U2") (pin "AA10") (pinfunction "VDDQ_AA10_AA10") (pintype "power_in"))
      (node (ref "U2") (pin "AA3") (pinfunction "VDDQ_AA3_AA3") (pintype "power_in"))
      (node (ref "U2") (pin "AA5") (pinfunction "VDDQ_AA5_AA5") (pintype "power_in"))
      (node (ref "U2") (pin "AA8") (pinfunction "VDDQ_AA8_AA8") (pintype "power_in"))
      (node (ref "U2") (pin "AB4") (pinfunction "VDD2_AB4_AB4") (pintype "power_in"))
      (node (ref "U2") (pin "AB9") (pinfunction "VDD2_AB9_AB9") (pintype "power_in"))
      (node (ref "U2") (pin "B10") (pinfunction "VDDQ_B10_B10") (pintype "power_in"))
      (node (ref "U2") (pin "B3") (pinfunction "VDDQ_B3_B3") (pintype "power_in"))
      (node (ref "U2") (pin "B5") (pinfunction "VDDQ_B5_B5") (pintype "power_in"))
      (node (ref "U2") (pin "B8") (pinfunction "VDDQ_B8_B8") (pintype "power_in"))
      (node (ref "U2") (pin "D1") (pinfunction "VDDQ_D1_D1") (pintype "power_in"))
      (node (ref "U2") (pin "D12") (pinfunction "VDDQ_D12_D12") (pintype "power_in"))
      (node (ref "U2") (pin "D5") (pinfunction "VDDQ_D5_D5") (pintype "power_in"))
      (node (ref "U2") (pin "D8") (pinfunction "VDDQ_D8_D8") (pintype "power_in"))
      (node (ref "U2") (pin "F10") (pinfunction "VDDQ_F10_F10") (pintype "power_in"))
      (node (ref "U2") (pin "F3") (pinfunction "VDDQ_F3_F3") (pintype "power_in"))
      (node (ref "U2") (pin "F5") (pinfunction "VDD2_F5_F5") (pintype "power_in"))
      (node (ref "U2") (pin "F8") (pinfunction "VDD2_F8_F8") (pintype "power_in"))
      (node (ref "U2") (pin "G2") (pinfunction "ODT_CA_A_G2") (pintype "input"))
      (node (ref "U2") (pin "H1") (pinfunction "VDD2_H1_H1") (pintype "power_in"))
      (node (ref "U2") (pin "H12") (pinfunction "VDD2_H12_H12") (pintype "power_in"))
      (node (ref "U2") (pin "H5") (pinfunction "VDD2_H5_H5") (pintype "power_in"))
      (node (ref "U2") (pin "H8") (pinfunction "VDD2_H8_H8") (pintype "power_in"))
      (node (ref "U2") (pin "K1") (pinfunction "VDD2_K1_K1") (pintype "power_in"))
      (node (ref "U2") (pin "K10") (pinfunction "VDD2_K10_K10") (pintype "power_in"))
      (node (ref "U2") (pin "K12") (pinfunction "VDD2_K12_K12") (pintype "power_in"))
      (node (ref "U2") (pin "K3") (pinfunction "VDD2_K3_K3") (pintype "power_in"))
      (node (ref "U2") (pin "N1") (pinfunction "VDD2_N1_N1") (pintype "power_in"))
      (node (ref "U2") (pin "N10") (pinfunction "VDD2_N10_N10") (pintype "power_in"))
      (node (ref "U2") (pin "N12") (pinfunction "VDD2_N12_N12") (pintype "power_in"))
      (node (ref "U2") (pin "N3") (pinfunction "VDD2_N3_N3") (pintype "power_in"))
      (node (ref "U2") (pin "R1") (pinfunction "VDD2_R1_R1") (pintype "power_in"))
      (node (ref "U2") (pin "R12") (pinfunction "VDD2_R12_R12") (pintype "power_in"))
      (node (ref "U2") (pin "R5") (pinfunction "VDD2_R5_R5") (pintype "power_in"))
      (node (ref "U2") (pin "R8") (pinfunction "VDD2_R8_R8") (pintype "power_in"))
      (node (ref "U2") (pin "T2") (pinfunction "ODT_CA_B_T2") (pintype "input"))
      (node (ref "U2") (pin "U10") (pinfunction "VDDQ_U10_U10") (pintype "power_in"))
      (node (ref "U2") (pin "U3") (pinfunction "VDDQ_U3_U3") (pintype "power_in"))
      (node (ref "U2") (pin "U5") (pinfunction "VDD2_U5_U5") (pintype "power_in"))
      (node (ref "U2") (pin "U8") (pinfunction "VDD2_U8_U8") (pintype "power_in"))
      (node (ref "U2") (pin "W1") (pinfunction "VDDQ_W1_W1") (pintype "power_in"))
      (node (ref "U2") (pin "W12") (pinfunction "VDDQ_W12_W12") (pintype "power_in"))
      (node (ref "U2") (pin "W5") (pinfunction "VDDQ_W5_W5") (pintype "power_in"))
      (node (ref "U2") (pin "W8") (pinfunction "VDDQ_W8_W8") (pintype "power_in"))
    )
    (net (code "82") (name "VDD_1V8") (class "Default")
      (node (ref "C71") (pin "2") (pinfunction "2_2") (pintype "passive"))
      (node (ref "C72") (pin "2") (pinfunction "2_2") (pintype "passive"))
      (node (ref "C73") (pin "2") (pinfunction "2_2") (pintype "passive"))
      (node (ref "C74") (pin "2") (pinfunction "2_2") (pintype "passive"))
      (node (ref "C75") (pin "2") (pinfunction "2_2") (pintype "passive"))
      (node (ref "C76") (pin "2") (pinfunction "2_2") (pintype "passive"))
      (node (ref "U2") (pin "F1") (pinfunction "VDD1_F1_F1") (pintype "power_in"))
      (node (ref "U2") (pin "F12") (pinfunction "VDD1_F12_F12") (pintype "power_in"))
      (node (ref "U2") (pin "G4") (pinfunction "VDD1_G4_G4") (pintype "power_in"))
      (node (ref "U2") (pin "G9") (pinfunction "VDD1_G9_G9") (pintype "power_in"))
      (node (ref "U2") (pin "T4") (pinfunction "VDD1_T4_T4") (pintype "power_in"))
      (node (ref "U2") (pin "T9") (pinfunction "VDD1_T9_T9") (pintype "power_in"))
      (node (ref "U2") (pin "U1") (pinfunction "VDD1_U1_U1") (pintype "power_in"))
      (node (ref "U2") (pin "U12") (pinfunction "VDD1_U12_U12") (pintype "power_in"))
    )
    (net (code "83") (name "unconnected-(U2A-DNU_A1-PadA1)") (class "Default")
      (node (ref "U2") (pin "A1") (pinfunction "DNU_A1_A1") (pintype "passive+no_connect"))
    )
    (net (code "84") (name "unconnected-(U2A-DNU_A2-PadA2)") (class "Default")
      (node (ref "U2") (pin "A2") (pinfunction "DNU_A2_A2") (pintype "passive+no_connect"))
    )
    (net (code "85") (name "unconnected-(U2A-DNU_A11-PadA11)") (class "Default")
      (node (ref "U2") (pin "A11") (pinfunction "DNU_A11_A11") (pintype "passive+no_connect"))
    )
    (net (code "86") (name "unconnected-(U2A-DNU_A12-PadA12)") (class "Default")
      (node (ref "U2") (pin "A12") (pinfunction "DNU_A12_A12") (pintype "passive+no_connect"))
    )
    (net (code "87") (name "unconnected-(U2A-DNU_AA1-PadAA1)") (class "Default")
      (node (ref "U2") (pin "AA1") (pinfunction "DNU_AA1_AA1") (pintype "passive+no_connect"))
    )
    (net (code "88") (name "unconnected-(U2A-DNU_AA12-PadAA12)") (class "Default")
      (node (ref "U2") (pin "AA12") (pinfunction "DNU_AA12_AA12") (pintype "passive+no_connect"))
    )
    (net (code "89") (name "unconnected-(U2A-DNU_AB1-PadAB1)") (class "Default")
      (node (ref "U2") (pin "AB1") (pinfunction "DNU_AB1_AB1") (pintype "passive+no_connect"))
    )
    (net (code "90") (name "unconnected-(U2A-DNU_AB2-PadAB2)") (class "Default")
      (node (ref "U2") (pin "AB2") (pinfunction "DNU_AB2_AB2") (pintype "passive+no_connect"))
    )
    (net (code "91") (name "unconnected-(U2A-DNU_AB11-PadAB11)") (class "Default")
      (node (ref "U2") (pin "AB11") (pinfunction "DNU_AB11_AB11") (pintype "passive+no_connect"))
    )
    (net (code "92") (name "unconnected-(U2A-DNU_AB12-PadAB12)") (class "Default")
      (node (ref "U2") (pin "AB12") (pinfunction "DNU_AB12_AB12") (pintype "passive+no_connect"))
    )
    (net (code "93") (name "unconnected-(U2A-DNU_B1-PadB1)") (class "Default")
      (node (ref "U2") (pin "B1") (pinfunction "DNU_B1_B1") (pintype "passive+no_connect"))
    )
    (net (code "94") (name "unconnected-(U2A-DNU_B12-PadB12)") (class "Default")
      (node (ref "U2") (pin "B12") (pinfunction "DNU_B12_B12") (pintype "passive+no_connect"))
    )
    (net (code "95") (name "unconnected-(U2A-NC_G11-PadG11)") (class "Default")
      (node (ref "U2") (pin "G11") (pinfunction "NC_G11_G11") (pintype "passive+no_connect"))
    )
    (net (code "96") (name "unconnected-(U2A-NC_K5-PadK5)") (class "Default")
      (node (ref "U2") (pin "K5") (pinfunction "NC_K5_K5") (pintype "passive+no_connect"))
    )
    (net (code "97") (name "unconnected-(U2A-NC_K8-PadK8)") (class "Default")
      (node (ref "U2") (pin "K8") (pinfunction "NC_K8_K8") (pintype "passive+no_connect"))
    )
    (net (code "98") (name "unconnected-(U2A-NC_N5-PadN5)") (class "Default")
      (node (ref "U2") (pin "N5") (pinfunction "NC_N5_N5") (pintype "passive+no_connect"))
    )
    (net (code "99") (name "unconnected-(U2A-NC_N8-PadN8)") (class "Default")
      (node (ref "U2") (pin "N8") (pinfunction "NC_N8_N8") (pintype "passive+no_connect"))
    )
  )
)
